# NMPaviIMU.net
KiCad netlist of a schematic drawn in EAGLE
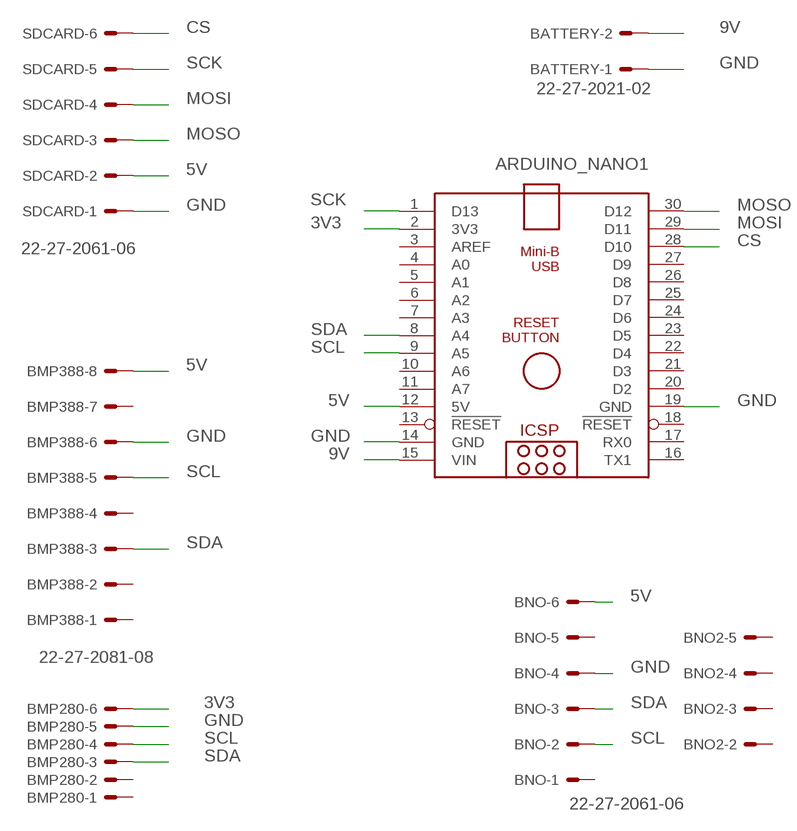
[diagram p0: schematic, sheet 1]

(export (version "E")
  (design (tool "Eeschema 10.0.6"))
  (components
    (comp (ref "ARDUINO_NANO1")
      (value "ARDUINO_NANO")
      (footprint "eagle-import:ARDUINO_NANO")
      (libsource (lib "eagle-import") (part "ARDUINO_NANO"))
    )
    (comp (ref "BATTERY")
      (value "22-27-2021-02")
      (footprint "eagle-import:6410-02")
      (fields (field (name "MF") "MOLEX"))
      (libsource (lib "eagle-import") (part "22-?-0227-2021"))
    )
    (comp (ref "BMP280")
      (value "22-23-2061")
      (footprint "eagle-import:22-23-2061")
      (fields (field (name "MF") "MOLEX"))
      (libsource (lib "eagle-import") (part "22-23-2061"))
    )
    (comp (ref "BMP388")
      (value "22-27-2081-08")
      (footprint "eagle-import:6410-08")
      (fields (field (name "MF") "MOLEX"))
      (libsource (lib "eagle-import") (part "22-?-0827-2081"))
    )
    (comp (ref "BNO")
      (value "22-27-2061-06")
      (footprint "eagle-import:6410-06")
      (fields (field (name "MF") "MOLEX"))
      (libsource (lib "eagle-import") (part "22-?-0627-2061"))
    )
    (comp (ref "BNO2")
      (value "22-27-2061-06")
      (footprint "eagle-import:6410-06")
      (fields (field (name "MF") "MOLEX"))
      (libsource (lib "eagle-import") (part "22-?-0627-2061"))
    )
    (comp (ref "SDCARD")
      (value "22-27-2061-06")
      (footprint "eagle-import:6410-06")
      (fields (field (name "MF") "MOLEX"))
      (libsource (lib "eagle-import") (part "22-?-0627-2061"))
    )
  )
  (nets
    (net (code "1") (name "3V3") (class "Default")
      (node (ref "ARDUINO_NANO1") (pin "2") (pinfunction "3V3_2") (pintype "output"))
      (node (ref "BMP280") (pin "6") (pinfunction "S_6") (pintype "passive"))
    )
    (net (code "2") (name "5V") (class "Default")
      (node (ref "ARDUINO_NANO1") (pin "12") (pinfunction "5V_12") (pintype "power_in"))
      (node (ref "BMP388") (pin "8") (pinfunction "S_8") (pintype "passive"))
      (node (ref "BNO") (pin "6") (pinfunction "S_6") (pintype "passive"))
      (node (ref "SDCARD") (pin "2") (pinfunction "S_2") (pintype "passive"))
    )
    (net (code "3") (name "9V") (class "Default")
      (node (ref "ARDUINO_NANO1") (pin "15") (pinfunction "VIN_15") (pintype "power_in"))
      (node (ref "BATTERY") (pin "2") (pinfunction "S_2") (pintype "passive"))
    )
    (net (code "4") (name "CS") (class "Default")
      (node (ref "ARDUINO_NANO1") (pin "28") (pinfunction "D10_28") (pintype "bidirectional"))
      (node (ref "SDCARD") (pin "6") (pinfunction "S_6") (pintype "passive"))
    )
    (net (code "5") (name "GND") (class "Default")
      (node (ref "ARDUINO_NANO1") (pin "14") (pinfunction "GND_14") (pintype "power_in"))
      (node (ref "ARDUINO_NANO1") (pin "19") (pinfunction "GND_19") (pintype "power_in"))
      (node (ref "BATTERY") (pin "1") (pinfunction "S_1") (pintype "passive"))
      (node (ref "BMP280") (pin "5") (pinfunction "S_5") (pintype "passive"))
      (node (ref "BMP388") (pin "6") (pinfunction "S_6") (pintype "passive"))
      (node (ref "BNO") (pin "4") (pinfunction "S_4") (pintype "passive"))
      (node (ref "SDCARD") (pin "1") (pinfunction "S_1") (pintype "passive"))
    )
    (net (code "6") (name "MOSI") (class "Default")
      (node (ref "ARDUINO_NANO1") (pin "29") (pinfunction "D11_29") (pintype "bidirectional"))
      (node (ref "SDCARD") (pin "4") (pinfunction "S_4") (pintype "passive"))
    )
    (net (code "7") (name "MOSO") (class "Default")
      (node (ref "ARDUINO_NANO1") (pin "30") (pinfunction "D12_30") (pintype "bidirectional"))
      (node (ref "SDCARD") (pin "3") (pinfunction "S_3") (pintype "passive"))
    )
    (net (code "8") (name "SCK") (class "Default")
      (node (ref "ARDUINO_NANO1") (pin "1") (pinfunction "D13_1") (pintype "bidirectional"))
      (node (ref "SDCARD") (pin "5") (pinfunction "S_5") (pintype "passive"))
    )
    (net (code "9") (name "SCL") (class "Default")
      (node (ref "ARDUINO_NANO1") (pin "9") (pinfunction "A5_9") (pintype "bidirectional"))
      (node (ref "BMP280") (pin "4") (pinfunction "S_4") (pintype "passive"))
      (node (ref "BMP388") (pin "5") (pinfunction "S_5") (pintype "passive"))
      (node (ref "BNO") (pin "2") (pinfunction "S_2") (pintype "passive"))
    )
    (net (code "10") (name "SDA") (class "Default")
      (node (ref "ARDUINO_NANO1") (pin "8") (pinfunction "A4_8") (pintype "bidirectional"))
      (node (ref "BMP280") (pin "3") (pinfunction "S_3") (pintype "passive"))
      (node (ref "BMP388") (pin "3") (pinfunction "S_3") (pintype "passive"))
      (node (ref "BNO") (pin "3") (pinfunction "S_3") (pintype "passive"))
    )
    (net (code "11") (name "unconnected-(ARDUINO_NANO1-A0-Pad4)") (class "Default")
      (node (ref "ARDUINO_NANO1") (pin "4") (pinfunction "A0_4") (pintype "bidirectional"))
    )
    (net (code "12") (name "unconnected-(ARDUINO_NANO1-A1-Pad5)") (class "Default")
      (node (ref "ARDUINO_NANO1") (pin "5") (pinfunction "A1_5") (pintype "bidirectional"))
    )
    (net (code "13") (name "unconnected-(ARDUINO_NANO1-A2-Pad6)") (class "Default")
      (node (ref "ARDUINO_NANO1") (pin "6") (pinfunction "A2_6") (pintype "bidirectional"))
    )
    (net (code "14") (name "unconnected-(ARDUINO_NANO1-A3-Pad7)") (class "Default")
      (node (ref "ARDUINO_NANO1") (pin "7") (pinfunction "A3_7") (pintype "bidirectional"))
    )
    (net (code "15") (name "unconnected-(ARDUINO_NANO1-A6-Pad10)") (class "Default")
      (node (ref "ARDUINO_NANO1") (pin "10") (pinfunction "A6_10") (pintype "bidirectional"))
    )
    (net (code "16") (name "unconnected-(ARDUINO_NANO1-A7-Pad11)") (class "Default")
      (node (ref "ARDUINO_NANO1") (pin "11") (pinfunction "A7_11") (pintype "bidirectional"))
    )
    (net (code "17") (name "unconnected-(ARDUINO_NANO1-AREF-Pad3)") (class "Default")
      (node (ref "ARDUINO_NANO1") (pin "3") (pinfunction "AREF_3") (pintype "input"))
    )
    (net (code "18") (name "unconnected-(ARDUINO_NANO1-D2-Pad20)") (class "Default")
      (node (ref "ARDUINO_NANO1") (pin "20") (pinfunction "D2_20") (pintype "bidirectional"))
    )
    (net (code "19") (name "unconnected-(ARDUINO_NANO1-D3-Pad21)") (class "Default")
      (node (ref "ARDUINO_NANO1") (pin "21") (pinfunction "D3_21") (pintype "bidirectional"))
    )
    (net (code "20") (name "unconnected-(ARDUINO_NANO1-D4-Pad22)") (class "Default")
      (node (ref "ARDUINO_NANO1") (pin "22") (pinfunction "D4_22") (pintype "bidirectional"))
    )
    (net (code "21") (name "unconnected-(ARDUINO_NANO1-D5-Pad23)") (class "Default")
      (node (ref "ARDUINO_NANO1") (pin "23") (pinfunction "D5_23") (pintype "bidirectional"))
    )
    (net (code "22") (name "unconnected-(ARDUINO_NANO1-D6-Pad24)") (class "Default")
      (node (ref "ARDUINO_NANO1") (pin "24") (pinfunction "D6_24") (pintype "bidirectional"))
    )
    (net (code "23") (name "unconnected-(ARDUINO_NANO1-D7-Pad25)") (class "Default")
      (node (ref "ARDUINO_NANO1") (pin "25") (pinfunction "D7_25") (pintype "bidirectional"))
    )
    (net (code "24") (name "unconnected-(ARDUINO_NANO1-D8-Pad26)") (class "Default")
      (node (ref "ARDUINO_NANO1") (pin "26") (pinfunction "D8_26") (pintype "bidirectional"))
    )
    (net (code "25") (name "unconnected-(ARDUINO_NANO1-D9-Pad27)") (class "Default")
      (node (ref "ARDUINO_NANO1") (pin "27") (pinfunction "D9_27") (pintype "bidirectional"))
    )
    (net (code "26") (name "unconnected-(ARDUINO_NANO1-RX0-Pad17)") (class "Default")
      (node (ref "ARDUINO_NANO1") (pin "17") (pinfunction "RX0_17") (pintype "bidirectional"))
    )
    (net (code "27") (name "unconnected-(ARDUINO_NANO1-TX1-Pad16)") (class "Default")
      (node (ref "ARDUINO_NANO1") (pin "16") (pinfunction "TX1_16") (pintype "bidirectional"))
    )
    (net (code "28") (name "unconnected-(ARDUINO_NANO1-~{RESET}-Pad13)") (class "Default")
      (node (ref "ARDUINO_NANO1") (pin "13") (pinfunction "~{RESET}_13") (pintype "input"))
    )
    (net (code "29") (name "unconnected-(ARDUINO_NANO1-~{RESET}-Pad18)") (class "Default")
      (node (ref "ARDUINO_NANO1") (pin "18") (pinfunction "~{RESET}_18") (pintype "input"))
    )
    (net (code "30") (name "unconnected-(BMP280A-S-Pad1)") (class "Default")
      (node (ref "BMP280") (pin "1") (pinfunction "S_1") (pintype "passive"))
    )
    (net (code "31") (name "unconnected-(BMP280B-S-Pad2)") (class "Default")
      (node (ref "BMP280") (pin "2") (pinfunction "S_2") (pintype "passive"))
    )
    (net (code "32") (name "unconnected-(BMP388A-S-Pad1)") (class "Default")
      (node (ref "BMP388") (pin "1") (pinfunction "S_1") (pintype "passive"))
    )
    (net (code "33") (name "unconnected-(BMP388B-S-Pad2)") (class "Default")
      (node (ref "BMP388") (pin "2") (pinfunction "S_2") (pintype "passive"))
    )
    (net (code "34") (name "unconnected-(BMP388D-S-Pad4)") (class "Default")
      (node (ref "BMP388") (pin "4") (pinfunction "S_4") (pintype "passive"))
    )
    (net (code "35") (name "unconnected-(BMP388G-S-Pad7)") (class "Default")
      (node (ref "BMP388") (pin "7") (pinfunction "S_7") (pintype "passive"))
    )
    (net (code "36") (name "unconnected-(BNO2B-S-Pad2)") (class "Default")
      (node (ref "BNO2") (pin "2") (pinfunction "S_2") (pintype "passive"))
    )
    (net (code "37") (name "unconnected-(BNO2C-S-Pad3)") (class "Default")
      (node (ref "BNO2") (pin "3") (pinfunction "S_3") (pintype "passive"))
    )
    (net (code "38") (name "unconnected-(BNO2D-S-Pad4)") (class "Default")
      (node (ref "BNO2") (pin "4") (pinfunction "S_4") (pintype "passive"))
    )
    (net (code "39") (name "unconnected-(BNO2E-S-Pad5)") (class "Default")
      (node (ref "BNO2") (pin "5") (pinfunction "S_5") (pintype "passive"))
    )
    (net (code "40") (name "unconnected-(BNOA-S-Pad1)") (class "Default")
      (node (ref "BNO") (pin "1") (pinfunction "S_1") (pintype "passive"))
    )
    (net (code "41") (name "unconnected-(BNOE-S-Pad5)") (class "Default")
      (node (ref "BNO") (pin "5") (pinfunction "S_5") (pintype "passive"))
    )
  )
)
